# misc.net
KiCad netlist of a schematic drawn in Altium Designer
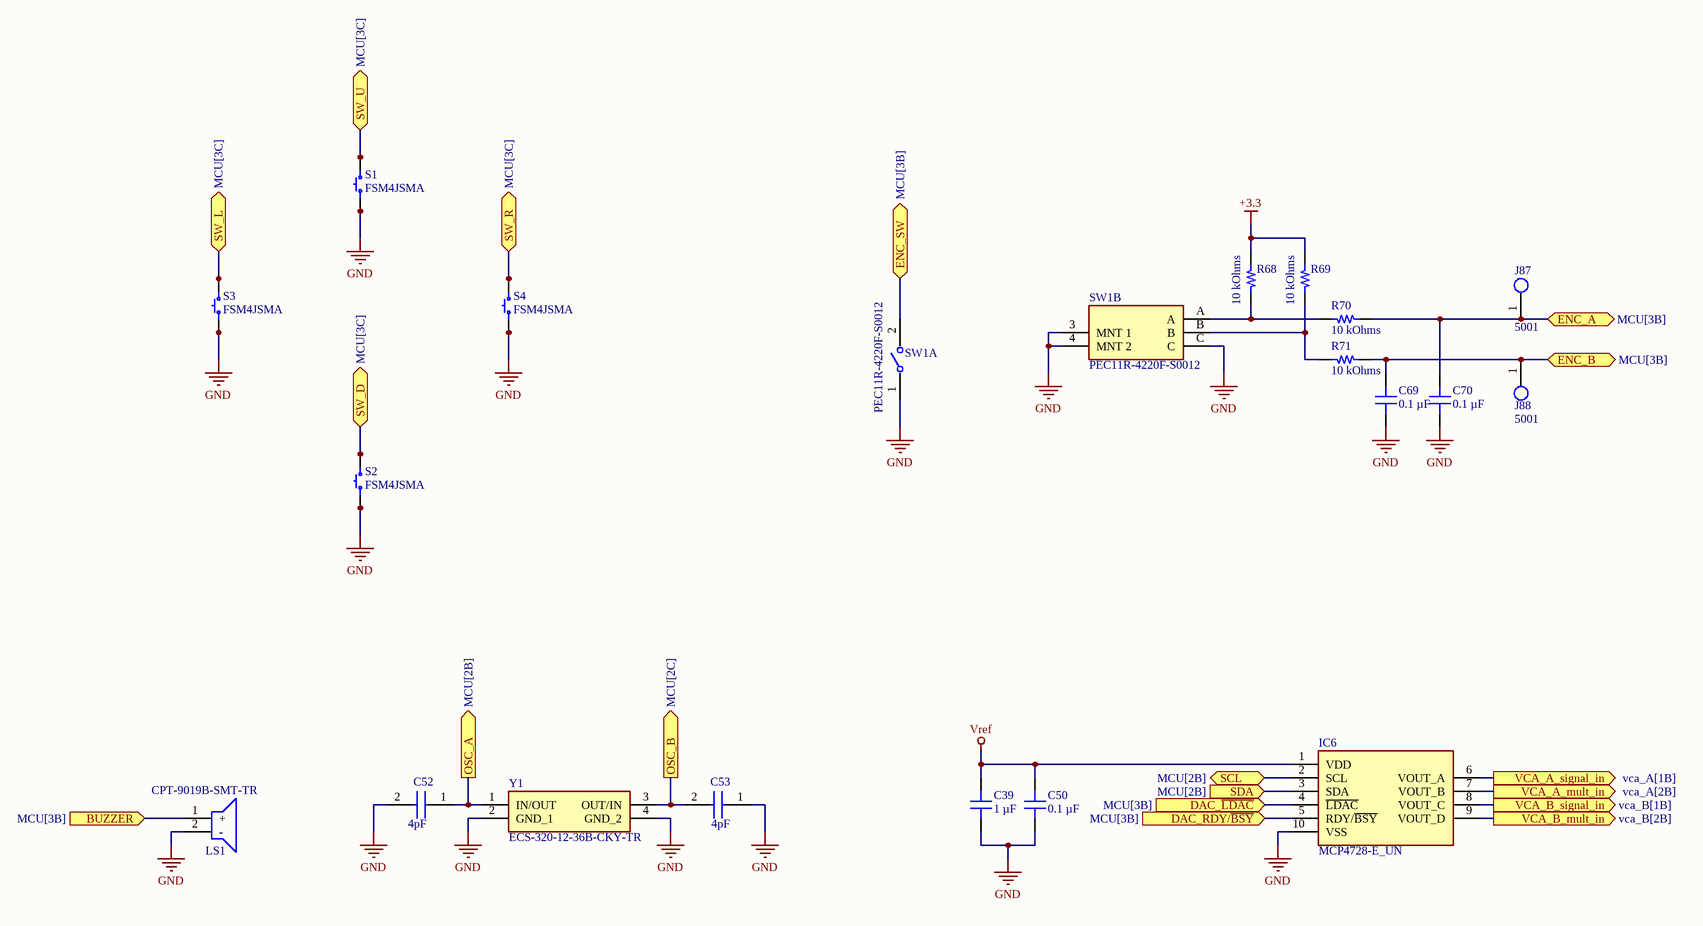
[diagram p0: misc.SchDoc]

(export (version "E")
  (design (tool "Eeschema 10.0.6"))
  (components
    (comp (ref "C39")
      (value "1 µF")
      (footprint "CAP 1206_3216 - 0.8MM")
      (description "CAP CER 1UF 50V X7R 1206")
      (fields
        (field (name "PART NUMBER") "885012208093")
        (field (name "CAPACITANCE") "1 µF")
        (field (name "MANUFACTURER") "Würth Elektronik")
      )
      (libsource (lib "Celestial Altium Library - altium_library") (part "Capacitor"))
    )
    (comp (ref "C50")
      (value "0.1 µF")
      (footprint "CAP 1206_3216 - 0.8MM")
      (description "CAP CER 0.1UF 50V X7R 1206")
      (fields
        (field (name "PART NUMBER") "885012208087")
        (field (name "CAPACITANCE") "0.1 µF")
        (field (name "MANUFACTURER") "Würth Elektronik")
      )
      (libsource (lib "Celestial Altium Library - altium_library") (part "Capacitor"))
    )
    (comp (ref "C52")
      (value "4pF")
      (footprint "CAPC1608X80N")
      (description "Capacitor")
      (fields (field (name "MANUFACTURER_PART_NUMBER") "C1608C0G1H040C080AA"))
      (libsource (lib "za_koncar") (part "C1608C0G1H040C080AA"))
    )
    (comp (ref "C53")
      (value "4pF")
      (footprint "CAPC1608X80N")
      (description "Capacitor")
      (fields (field (name "MANUFACTURER_PART_NUMBER") "C1608C0G1H040C080AA"))
      (libsource (lib "za_koncar") (part "C1608C0G1H040C080AA"))
    )
    (comp (ref "C69")
      (value "0.1 µF")
      (footprint "CAP 1206_3216 - 0.8MM")
      (description "CAP CER 0.1UF 50V X7R 1206")
      (fields
        (field (name "PART NUMBER") "885012208087")
        (field (name "CAPACITANCE") "0.1 µF")
        (field (name "MANUFACTURER") "Würth Elektronik")
      )
      (libsource (lib "Celestial Altium Library - altium_library") (part "Capacitor"))
    )
    (comp (ref "C70")
      (value "0.1 µF")
      (footprint "CAP 1206_3216 - 0.8MM")
      (description "CAP CER 0.1UF 50V X7R 1206")
      (fields
        (field (name "PART NUMBER") "885012208087")
        (field (name "CAPACITANCE") "0.1 µF")
        (field (name "MANUFACTURER") "Würth Elektronik")
      )
      (libsource (lib "Celestial Altium Library - altium_library") (part "Capacitor"))
    )
    (comp (ref "IC6")
      (value "MCP4728-E_UN")
      (footprint "SOP50P490X110-10N")
      (description "Integrated Circuit")
      (fields
        (field (name "MANUFACTURER_PART_NUMBER") "MCP4728-E/UN")
        (field (name "MOUSER PART NUMBER") "579-MCP4728-E/UN")
      )
      (libsource (lib "za_koncar") (part "MCP4728-E_UN"))
    )
    (comp (ref "J87")
      (value "5001")
      (footprint "FP-5001-MFG")
      (description "PC TEST POINT MINIATURE BLACK")
      (libsource (lib "za_koncar") (part "CMP-2000-05181-2"))
    )
    (comp (ref "J88")
      (value "5001")
      (footprint "FP-5001-MFG")
      (description "PC TEST POINT MINIATURE BLACK")
      (libsource (lib "za_koncar") (part "CMP-2000-05181-2"))
    )
    (comp (ref "LS1")
      (value "CPT-9019B-SMT-TR")
      (footprint "CPT9019BSMTTR")
      (description "Loudspeaker or Buzzer")
      (fields (field (name "MOUSER PART NUMBER") "179-CPT-9019B-SMT-TR"))
      (libsource (lib "za_koncar") (part "CPT-9019B-SMT-TR"))
    )
    (comp (ref "R68")
      (value "10 kOhms")
      (footprint "YAGEO RES 1206_3216")
      (description "RES SMD 10K OHM 1% 1/4W 1206")
      (fields (field (name "PART NUMBER") "RT1206FRE0710KL") (field (name "MANUFACTURER") "Yageo"))
      (libsource (lib "Celestial Altium Library - altium_library") (part "Resistor"))
    )
    (comp (ref "R69")
      (value "10 kOhms")
      (footprint "YAGEO RES 1206_3216")
      (description "RES SMD 10K OHM 1% 1/4W 1206")
      (fields (field (name "PART NUMBER") "RT1206FRE0710KL") (field (name "MANUFACTURER") "Yageo"))
      (libsource (lib "Celestial Altium Library - altium_library") (part "Resistor"))
    )
    (comp (ref "R70")
      (value "10 kOhms")
      (footprint "YAGEO RES 1206_3216")
      (description "RES SMD 10K OHM 1% 1/4W 1206")
      (fields (field (name "PART NUMBER") "RT1206FRE0710KL") (field (name "MANUFACTURER") "Yageo"))
      (libsource (lib "Celestial Altium Library - altium_library") (part "Resistor"))
    )
    (comp (ref "R71")
      (value "10 kOhms")
      (footprint "YAGEO RES 1206_3216")
      (description "RES SMD 10K OHM 1% 1/4W 1206")
      (fields (field (name "PART NUMBER") "RT1206FRE0710KL") (field (name "MANUFACTURER") "Yageo"))
      (libsource (lib "Celestial Altium Library - altium_library") (part "Resistor"))
    )
    (comp (ref "S1")
      (value "FSM4JSMA")
      (footprint "TE FSM4JSMA")
      (description "SWITCH TACTILE SPST-NO 0.05A 24V")
      (fields (field (name "MANUFACTURER") "TE Connectivity ALCOSWITCH Switches"))
      (libsource (lib "Celestial Altium Library - altium_library") (part "SPST-NO 4 PIN"))
    )
    (comp (ref "S2")
      (value "FSM4JSMA")
      (footprint "TE FSM4JSMA")
      (description "SWITCH TACTILE SPST-NO 0.05A 24V")
      (fields (field (name "MANUFACTURER") "TE Connectivity ALCOSWITCH Switches"))
      (libsource (lib "Celestial Altium Library - altium_library") (part "SPST-NO 4 PIN"))
    )
    (comp (ref "S3")
      (value "FSM4JSMA")
      (footprint "TE FSM4JSMA")
      (description "SWITCH TACTILE SPST-NO 0.05A 24V")
      (fields (field (name "MANUFACTURER") "TE Connectivity ALCOSWITCH Switches"))
      (libsource (lib "Celestial Altium Library - altium_library") (part "SPST-NO 4 PIN"))
    )
    (comp (ref "S4")
      (value "FSM4JSMA")
      (footprint "TE FSM4JSMA")
      (description "SWITCH TACTILE SPST-NO 0.05A 24V")
      (fields (field (name "MANUFACTURER") "TE Connectivity ALCOSWITCH Switches"))
      (libsource (lib "Celestial Altium Library - altium_library") (part "SPST-NO 4 PIN"))
    )
    (comp (ref "SW1")
      (value "PEC11R-4220F-S0012")
      (footprint "FP-PEC11R-4220F-S0012-MFG")
      (description "ROTARY ENCODER MECHANICAL 12PPR")
      (libsource (lib "za_koncar") (part "PEC11R-4220F-S0012"))
    )
    (comp (ref "Y1")
      (value "ECS-320-12-36B-CKY-TR")
      (footprint "ECS240836QAESTR")
      (description "Crystal or Oscillator")
      (fields (field (name "MOUSER PART NUMBER") "520-320-12-36B-CKYT"))
      (libsource (lib "za_koncar") (part "ECS-320-12-36B-CKY-TR"))
    )
  )
  (nets
    (net (code "1") (name "+3.3") (class "Default")
      (node (ref "R68") (pin "1") (pinfunction "1_1") (pintype "passive"))
      (node (ref "R69") (pin "1") (pinfunction "1_1") (pintype "passive"))
    )
    (net (code "2") (name "/BUZZER") (class "Default")
      (node (ref "LS1") (pin "1") (pinfunction "+_1") (pintype "passive"))
    )
    (net (code "3") (name "/DAC_RDY{slash}~{BSY}") (class "Default")
      (node (ref "IC6") (pin "5") (pinfunction "RDY/~{BSY}_5") (pintype "passive"))
    )
    (net (code "4") (name "/DAC_~{LDAC}") (class "Default")
      (node (ref "IC6") (pin "4") (pinfunction "~{LDAC}_4") (pintype "passive"))
    )
    (net (code "5") (name "/ENC_A") (class "Default")
      (node (ref "C70") (pin "2") (pinfunction "2_2") (pintype "passive"))
      (node (ref "J87") (pin "1") (pinfunction "1_1") (pintype "passive"))
      (node (ref "R70") (pin "2") (pinfunction "2_2") (pintype "passive"))
    )
    (net (code "6") (name "/ENC_B") (class "Default")
      (node (ref "C69") (pin "2") (pinfunction "2_2") (pintype "passive"))
      (node (ref "J88") (pin "1") (pinfunction "1_1") (pintype "passive"))
      (node (ref "R71") (pin "2") (pinfunction "2_2") (pintype "passive"))
    )
    (net (code "7") (name "/ENC_SW") (class "Default")
      (node (ref "SW1") (pin "2") (pinfunction "2_2") (pintype "passive"))
    )
    (net (code "8") (name "/OSC_A") (class "Default")
      (node (ref "C52") (pin "1") (pinfunction "1_1") (pintype "passive"))
      (node (ref "Y1") (pin "1") (pinfunction "IN/OUT_1") (pintype "passive"))
    )
    (net (code "9") (name "/OSC_B") (class "Default")
      (node (ref "C53") (pin "2") (pinfunction "2_2") (pintype "passive"))
      (node (ref "Y1") (pin "3") (pinfunction "OUT/IN_3") (pintype "passive"))
    )
    (net (code "10") (name "/SCL") (class "Default")
      (node (ref "IC6") (pin "2") (pinfunction "SCL_2") (pintype "passive"))
    )
    (net (code "11") (name "/SDA") (class "Default")
      (node (ref "IC6") (pin "3") (pinfunction "SDA_3") (pintype "passive"))
    )
    (net (code "12") (name "/SW_D") (class "Default")
      (node (ref "S2") (pin "3") (pinfunction "3_3") (pintype "passive"))
      (node (ref "S2") (pin "4") (pinfunction "4_4") (pintype "passive"))
    )
    (net (code "13") (name "/SW_L") (class "Default")
      (node (ref "S3") (pin "3") (pinfunction "3_3") (pintype "passive"))
      (node (ref "S3") (pin "4") (pinfunction "4_4") (pintype "passive"))
    )
    (net (code "14") (name "/SW_R") (class "Default")
      (node (ref "S4") (pin "3") (pinfunction "3_3") (pintype "passive"))
      (node (ref "S4") (pin "4") (pinfunction "4_4") (pintype "passive"))
    )
    (net (code "15") (name "/SW_U") (class "Default")
      (node (ref "S1") (pin "3") (pinfunction "3_3") (pintype "passive"))
      (node (ref "S1") (pin "4") (pinfunction "4_4") (pintype "passive"))
    )
    (net (code "16") (name "/VCA_A_mult_in") (class "Default")
      (node (ref "IC6") (pin "7") (pinfunction "VOUT_B_7") (pintype "passive"))
    )
    (net (code "17") (name "/VCA_A_signal_in") (class "Default")
      (node (ref "IC6") (pin "6") (pinfunction "VOUT_A_6") (pintype "passive"))
    )
    (net (code "18") (name "/VCA_B_mult_in") (class "Default")
      (node (ref "IC6") (pin "9") (pinfunction "VOUT_D_9") (pintype "passive"))
    )
    (net (code "19") (name "/VCA_B_signal_in") (class "Default")
      (node (ref "IC6") (pin "8") (pinfunction "VOUT_C_8") (pintype "passive"))
    )
    (net (code "20") (name "GND") (class "Default")
      (node (ref "C39") (pin "1") (pinfunction "1_1") (pintype "passive"))
      (node (ref "C50") (pin "1") (pinfunction "1_1") (pintype "passive"))
      (node (ref "C52") (pin "2") (pinfunction "2_2") (pintype "passive"))
      (node (ref "C53") (pin "1") (pinfunction "1_1") (pintype "passive"))
      (node (ref "C69") (pin "1") (pinfunction "1_1") (pintype "passive"))
      (node (ref "C70") (pin "1") (pinfunction "1_1") (pintype "passive"))
      (node (ref "IC6") (pin "10") (pinfunction "VSS_10") (pintype "passive"))
      (node (ref "LS1") (pin "2") (pinfunction "-_2") (pintype "passive"))
      (node (ref "S1") (pin "1") (pinfunction "1_1") (pintype "passive"))
      (node (ref "S1") (pin "2") (pinfunction "2_2") (pintype "passive"))
      (node (ref "S2") (pin "1") (pinfunction "1_1") (pintype "passive"))
      (node (ref "S2") (pin "2") (pinfunction "2_2") (pintype "passive"))
      (node (ref "S3") (pin "1") (pinfunction "1_1") (pintype "passive"))
      (node (ref "S3") (pin "2") (pinfunction "2_2") (pintype "passive"))
      (node (ref "S4") (pin "1") (pinfunction "1_1") (pintype "passive"))
      (node (ref "S4") (pin "2") (pinfunction "2_2") (pintype "passive"))
      (node (ref "SW1") (pin "1") (pinfunction "1_1") (pintype "passive"))
      (node (ref "SW1") (pin "3") (pinfunction "MNT_1_3") (pintype "passive"))
      (node (ref "SW1") (pin "4") (pinfunction "MNT_2_4") (pintype "passive"))
      (node (ref "SW1") (pin "C") (pinfunction "C_C") (pintype "passive"))
      (node (ref "Y1") (pin "2") (pinfunction "GND_1_2") (pintype "passive"))
      (node (ref "Y1") (pin "4") (pinfunction "GND_2_4") (pintype "passive"))
    )
    (net (code "21") (name "Net-(R68-Pad2)") (class "Default")
      (node (ref "R68") (pin "2") (pinfunction "2_2") (pintype "passive"))
      (node (ref "R70") (pin "1") (pinfunction "1_1") (pintype "passive"))
      (node (ref "SW1") (pin "A") (pinfunction "A_A") (pintype "passive"))
    )
    (net (code "22") (name "Net-(R69-Pad2)") (class "Default")
      (node (ref "R69") (pin "2") (pinfunction "2_2") (pintype "passive"))
      (node (ref "R71") (pin "1") (pinfunction "1_1") (pintype "passive"))
      (node (ref "SW1") (pin "B") (pinfunction "B_B") (pintype "passive"))
    )
    (net (code "23") (name "Vref") (class "Default")
      (node (ref "C39") (pin "2") (pinfunction "2_2") (pintype "passive"))
      (node (ref "C50") (pin "2") (pinfunction "2_2") (pintype "passive"))
      (node (ref "IC6") (pin "1") (pinfunction "VDD_1") (pintype "passive"))
    )
  )
)
